# Adafruit_Circuit_Playground_Bluefruit.net
KiCad netlist of a schematic drawn in EAGLE
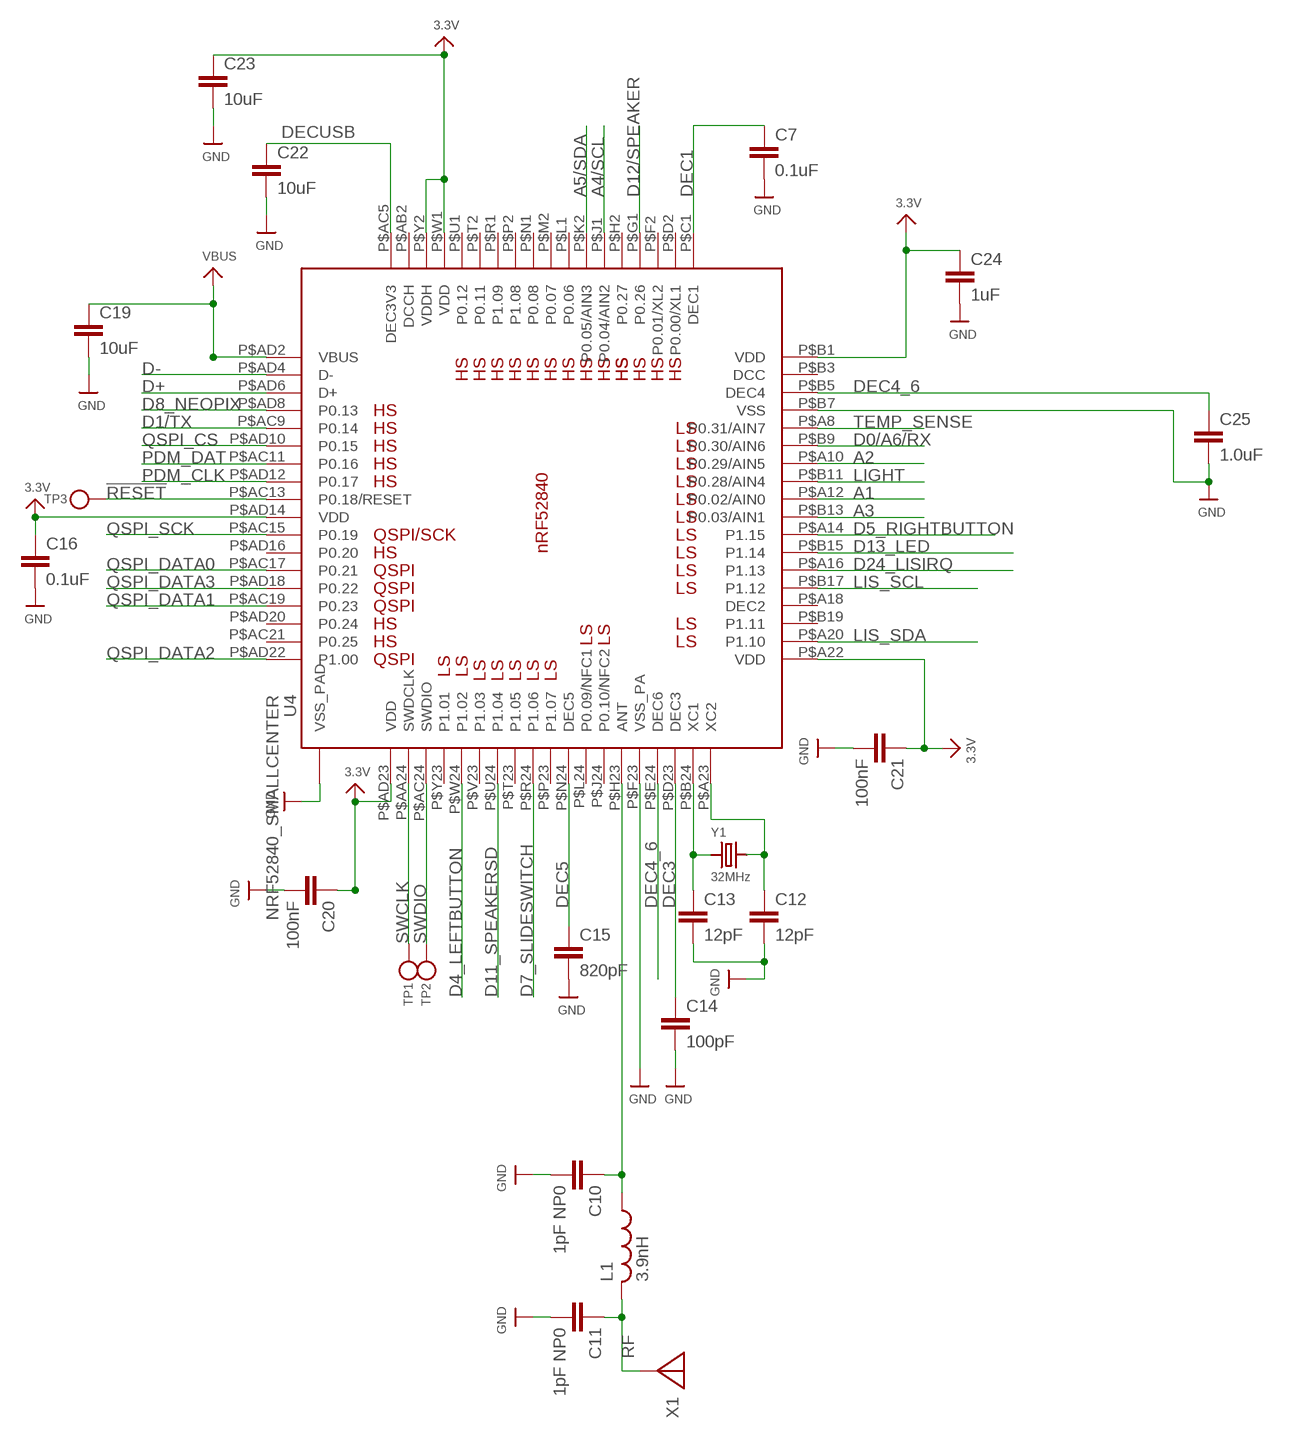
[diagram p0: schematic, sheet 1, part 1 of 2]
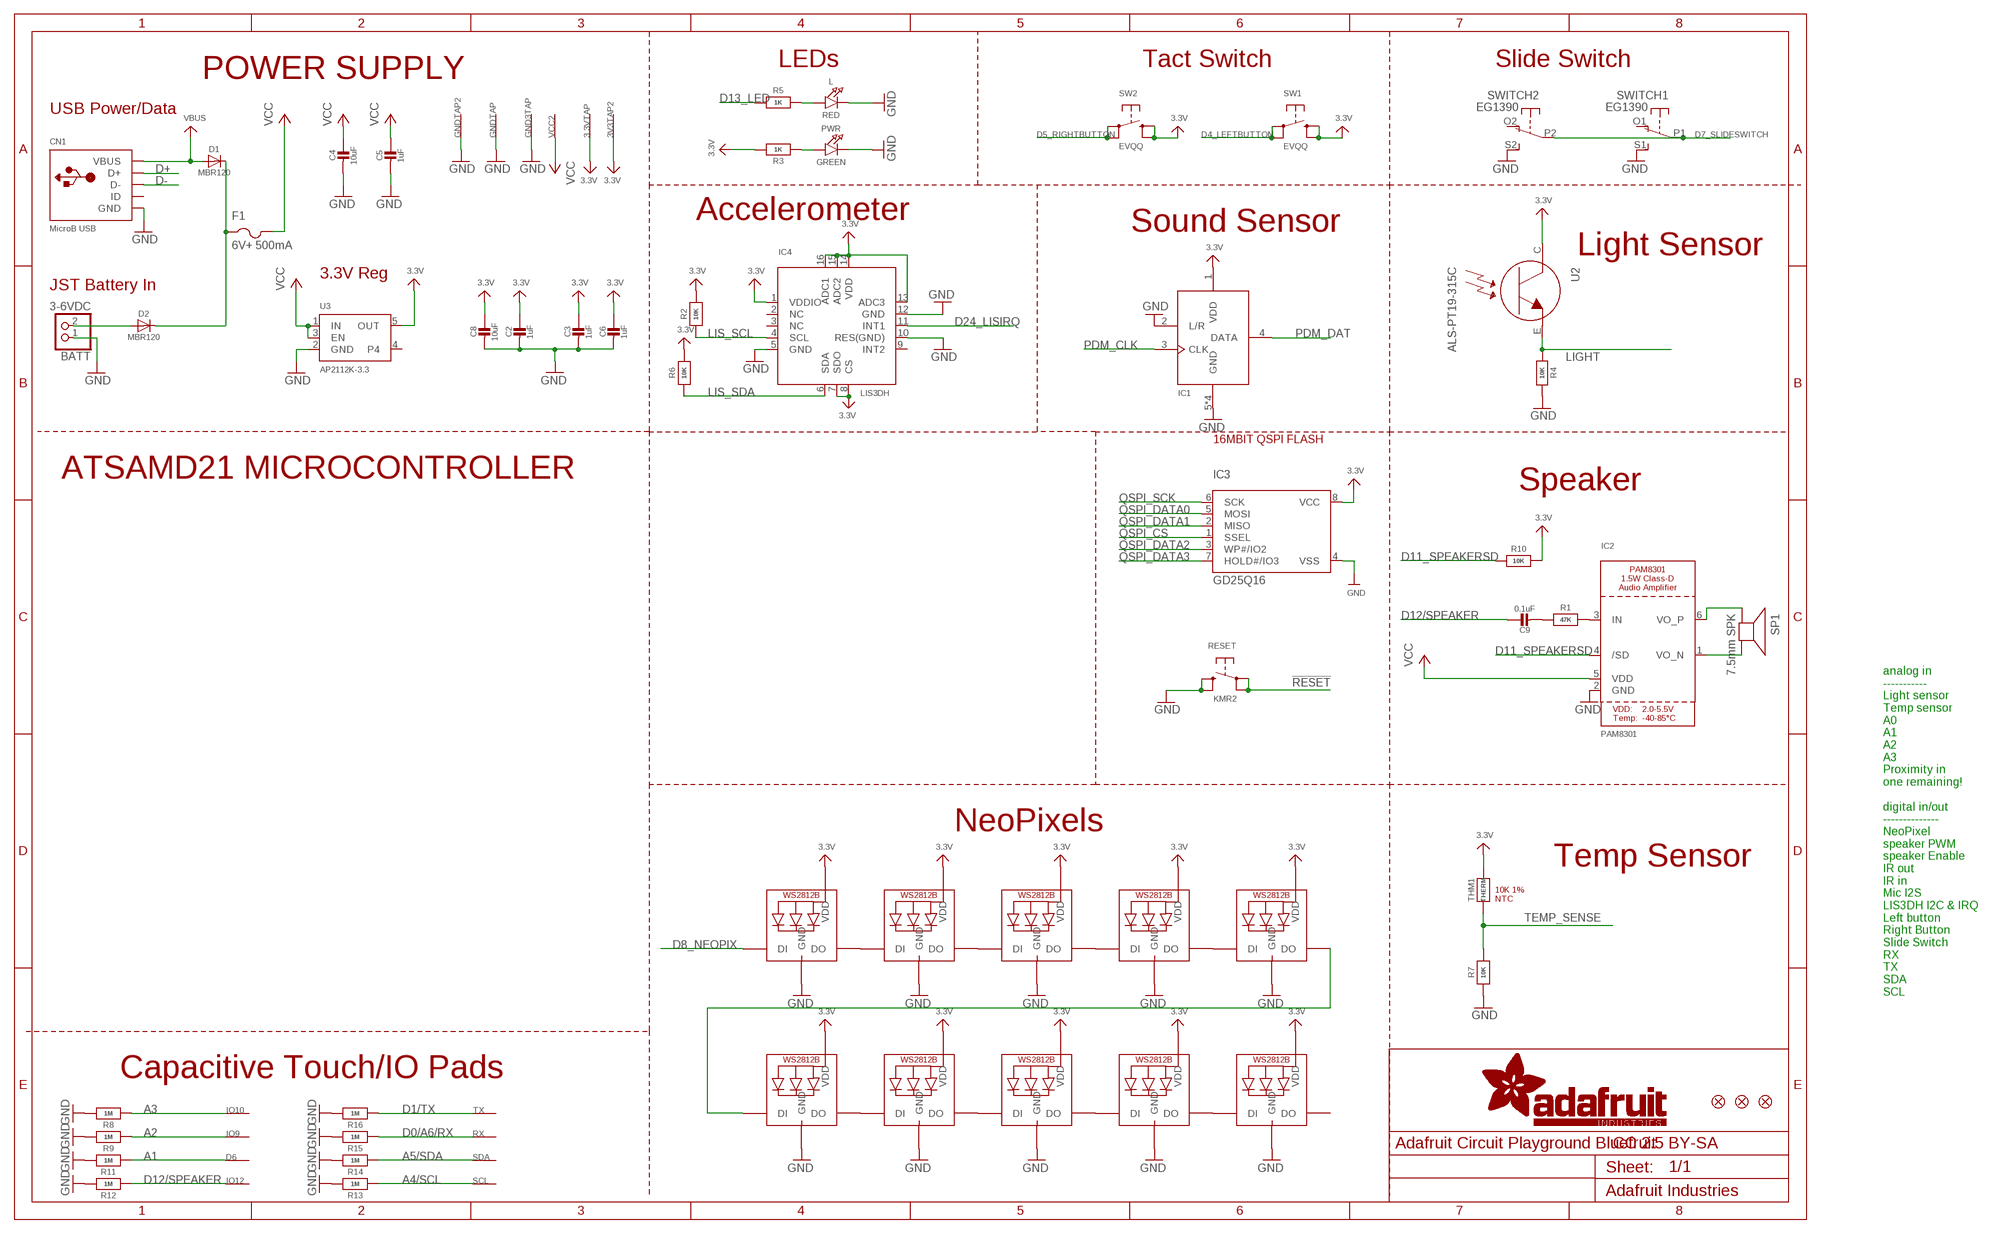
[diagram p1: schematic, sheet 1, part 2 of 2]

(export (version "E")
  (design (tool "Eeschema 10.0.6"))
  (components
    (comp (ref "3.3VTAP")
      (value "SEWTAP-ALLIGATOR")
      (footprint "eagle-import:SEWALLI")
      (libsource (lib "eagle-import") (part "SEWTAP-ALLIGATOR"))
    )
    (comp (ref "3V3TAP2")
      (value "SEWTAP-ALLIGATOR")
      (footprint "eagle-import:SEWALLI")
      (libsource (lib "eagle-import") (part "SEWTAP-ALLIGATOR"))
    )
    (comp (ref "BATT")
      (value "3-6VDC")
      (footprint "eagle-import:JSTPH2")
      (libsource (lib "eagle-import") (part "CON_JST_PH_2PIN"))
    )
    (comp (ref "C2")
      (value "1uF")
      (footprint "eagle-import:0603-NO")
      (libsource (lib "eagle-import") (part "CAP_CERAMIC0603_NO"))
    )
    (comp (ref "C3")
      (value "1uF")
      (footprint "eagle-import:0603-NO")
      (libsource (lib "eagle-import") (part "CAP_CERAMIC0603_NO"))
    )
    (comp (ref "C4")
      (value "10uF")
      (footprint "eagle-import:0805-NO")
      (libsource (lib "eagle-import") (part "CAP_CERAMIC0805-NOOUTLINE"))
    )
    (comp (ref "C5")
      (value "1uF")
      (footprint "eagle-import:0603-NO")
      (libsource (lib "eagle-import") (part "CAP_CERAMIC0603_NO"))
    )
    (comp (ref "C6")
      (value "1uF")
      (footprint "eagle-import:0603-NO")
      (libsource (lib "eagle-import") (part "CAP_CERAMIC0603_NO"))
    )
    (comp (ref "C7")
      (value "0.1uF")
      (footprint "eagle-import:RESC0603_N")
      (libsource (lib "eagle-import") (part "CAPACITOR_0603_N"))
    )
    (comp (ref "C8")
      (value "10uF")
      (footprint "eagle-import:0805-NO")
      (libsource (lib "eagle-import") (part "CAP_CERAMIC0805-NOOUTLINE"))
    )
    (comp (ref "C9")
      (value "0.1uF")
      (footprint "eagle-import:0603-NO")
      (libsource (lib "eagle-import") (part "CAP_CERAMIC0603_NO"))
    )
    (comp (ref "C10")
      (value "1pF NP0")
      (footprint "eagle-import:RESC0402_N")
      (libsource (lib "eagle-import") (part "CAPACITOR_0402_N"))
    )
    (comp (ref "C11")
      (value "1pF NP0")
      (footprint "eagle-import:RESC0402_N")
      (libsource (lib "eagle-import") (part "CAPACITOR_0402_N"))
    )
    (comp (ref "C12")
      (value "12pF")
      (footprint "eagle-import:RESC0402_N")
      (libsource (lib "eagle-import") (part "CAPACITOR_0402_N"))
    )
    (comp (ref "C13")
      (value "12pF")
      (footprint "eagle-import:RESC0402_N")
      (libsource (lib "eagle-import") (part "CAPACITOR_0402_N"))
    )
    (comp (ref "C14")
      (value "100pF")
      (footprint "eagle-import:RESC0402_N")
      (libsource (lib "eagle-import") (part "CAPACITOR_0402_N"))
    )
    (comp (ref "C15")
      (value "820pF")
      (footprint "eagle-import:RESC0402_N")
      (libsource (lib "eagle-import") (part "CAPACITOR_0402_N"))
    )
    (comp (ref "C16")
      (value "0.1uF")
      (footprint "eagle-import:RESC0402_N")
      (libsource (lib "eagle-import") (part "CAPACITOR_0402_N"))
    )
    (comp (ref "C19")
      (value "10uF")
      (footprint "eagle-import:RESC0805_N")
      (libsource (lib "eagle-import") (part "CAPACITOR_0805_N"))
    )
    (comp (ref "C20")
      (value "100nF")
      (footprint "eagle-import:RESC0402_N")
      (libsource (lib "eagle-import") (part "CAPACITOR_0402_N"))
    )
    (comp (ref "C21")
      (value "100nF")
      (footprint "eagle-import:RESC0402_N")
      (libsource (lib "eagle-import") (part "CAPACITOR_0402_N"))
    )
    (comp (ref "C22")
      (value "10uF")
      (footprint "eagle-import:RESC0805_N")
      (libsource (lib "eagle-import") (part "CAPACITOR_0805_N"))
    )
    (comp (ref "C23")
      (value "10uF")
      (footprint "eagle-import:RESC0805_N")
      (libsource (lib "eagle-import") (part "CAPACITOR_0805_N"))
    )
    (comp (ref "C24")
      (value "1uF")
      (footprint "eagle-import:RESC0603_N")
      (libsource (lib "eagle-import") (part "CAPACITOR_0603_N"))
    )
    (comp (ref "C25")
      (value "1.0uF")
      (footprint "eagle-import:RESC0603_N")
      (libsource (lib "eagle-import") (part "CAPACITOR_0603_N"))
    )
    (comp (ref "CN1")
      (value "MicroB USB")
      (footprint "eagle-import:4UCONN_20329_V2")
      (libsource (lib "eagle-import") (part "USB_MICRO_20329_V2"))
    )
    (comp (ref "D1")
      (value "MBR120")
      (footprint "eagle-import:SOD-123")
      (libsource (lib "eagle-import") (part "DIODESOD-123"))
    )
    (comp (ref "D2")
      (value "MBR120")
      (footprint "eagle-import:SOD-123")
      (libsource (lib "eagle-import") (part "DIODESOD-123"))
    )
    (comp (ref "D6")
      (value "SEWTAP-ALLIGATOR")
      (footprint "eagle-import:SEWALLI")
      (libsource (lib "eagle-import") (part "SEWTAP-ALLIGATOR"))
    )
    (comp (ref "F1")
      (value "6V+ 500mA")
      (footprint "eagle-import:R1206")
      (libsource (lib "eagle-import") (part "PTCFUSE-1206"))
    )
    (comp (ref "GND3TAP")
      (value "SEWTAP-ALLIGATOR")
      (footprint "eagle-import:SEWALLI")
      (libsource (lib "eagle-import") (part "SEWTAP-ALLIGATOR"))
    )
    (comp (ref "GNDTAP")
      (value "SEWTAP-ALLIGATOR")
      (footprint "eagle-import:SEWALLI")
      (libsource (lib "eagle-import") (part "SEWTAP-ALLIGATOR"))
    )
    (comp (ref "GNDTAP2")
      (value "SEWTAP-ALLIGATOR")
      (footprint "eagle-import:SEWALLI")
      (libsource (lib "eagle-import") (part "SEWTAP-ALLIGATOR"))
    )
    (comp (ref "IC1")
      (value "MIC_PDM")
      (footprint "eagle-import:SPK0415HM4H")
      (libsource (lib "eagle-import") (part "MIC_PDM_SPK0415"))
    )
    (comp (ref "IC2")
      (value "PAM8301")
      (footprint "eagle-import:SOT23-6")
      (libsource (lib "eagle-import") (part "PAM8301"))
    )
    (comp (ref "IC3")
      (value "GD25Q16")
      (footprint "eagle-import:USON8")
      (libsource (lib "eagle-import") (part "SPIFLASH_8PINUX"))
    )
    (comp (ref "IC4")
      (value "LIS3DH")
      (footprint "eagle-import:LGA16_3X3MM")
      (libsource (lib "eagle-import") (part "ACCEL_LIS3DHTR"))
    )
    (comp (ref "IO9")
      (value "SEWTAP-ALLIGATOR")
      (footprint "eagle-import:SEWALLI")
      (libsource (lib "eagle-import") (part "SEWTAP-ALLIGATOR"))
    )
    (comp (ref "IO10")
      (value "SEWTAP-ALLIGATOR")
      (footprint "eagle-import:SEWALLI")
      (libsource (lib "eagle-import") (part "SEWTAP-ALLIGATOR"))
    )
    (comp (ref "IO12")
      (value "SEWTAP-ALLIGATOR")
      (footprint "eagle-import:SEWALLI")
      (libsource (lib "eagle-import") (part "SEWTAP-ALLIGATOR"))
    )
    (comp (ref "L")
      (value "RED")
      (footprint "eagle-import:CHIPLED_0805_NOOUTLINE")
      (libsource (lib "eagle-import") (part "LED0805_NOOUTLINE"))
    )
    (comp (ref "L1")
      (value "3.9nH")
      (footprint "eagle-import:RESC0402_N")
      (libsource (lib "eagle-import") (part "INDUCTOR_0402_N"))
    )
    (comp (ref "LED1")
      (value "WS2812B3535")
      (footprint "eagle-import:LED3535")
      (libsource (lib "eagle-import") (part "WS2812B3535"))
    )
    (comp (ref "LED2")
      (value "WS2812B3535")
      (footprint "eagle-import:LED3535")
      (libsource (lib "eagle-import") (part "WS2812B3535"))
    )
    (comp (ref "LED3")
      (value "WS2812B3535")
      (footprint "eagle-import:LED3535")
      (libsource (lib "eagle-import") (part "WS2812B3535"))
    )
    (comp (ref "LED4")
      (value "WS2812B3535")
      (footprint "eagle-import:LED3535")
      (libsource (lib "eagle-import") (part "WS2812B3535"))
    )
    (comp (ref "LED5")
      (value "WS2812B3535")
      (footprint "eagle-import:LED3535")
      (libsource (lib "eagle-import") (part "WS2812B3535"))
    )
    (comp (ref "LED6")
      (value "WS2812B3535")
      (footprint "eagle-import:LED3535")
      (libsource (lib "eagle-import") (part "WS2812B3535"))
    )
    (comp (ref "LED7")
      (value "WS2812B3535")
      (footprint "eagle-import:LED3535")
      (libsource (lib "eagle-import") (part "WS2812B3535"))
    )
    (comp (ref "LED8")
      (value "WS2812B3535")
      (footprint "eagle-import:LED3535")
      (libsource (lib "eagle-import") (part "WS2812B3535"))
    )
    (comp (ref "LED9")
      (value "WS2812B3535")
      (footprint "eagle-import:LED3535")
      (libsource (lib "eagle-import") (part "WS2812B3535"))
    )
    (comp (ref "LED10")
      (value "WS2812B3535")
      (footprint "eagle-import:LED3535")
      (libsource (lib "eagle-import") (part "WS2812B3535"))
    )
    (comp (ref "PWR")
      (value "GREEN")
      (footprint "eagle-import:CHIPLED_0805_NOOUTLINE")
      (libsource (lib "eagle-import") (part "LED0805_NOOUTLINE"))
    )
    (comp (ref "R1")
      (value "47K")
      (footprint "eagle-import:0603-NO")
      (libsource (lib "eagle-import") (part "RESISTOR_0603_NOOUT"))
    )
    (comp (ref "R2")
      (value "10K")
      (footprint "eagle-import:0603-NO")
      (libsource (lib "eagle-import") (part "RESISTOR_0603_NOOUT"))
    )
    (comp (ref "R3")
      (value "1K")
      (footprint "eagle-import:0603-NO")
      (libsource (lib "eagle-import") (part "RESISTOR_0603_NOOUT"))
    )
    (comp (ref "R4")
      (value "10K")
      (footprint "eagle-import:0603-NO")
      (libsource (lib "eagle-import") (part "RESISTOR_0603_NOOUT"))
    )
    (comp (ref "R5")
      (value "1K")
      (footprint "eagle-import:0603-NO")
      (libsource (lib "eagle-import") (part "RESISTOR_0603_NOOUT"))
    )
    (comp (ref "R6")
      (value "10K")
      (footprint "eagle-import:0603-NO")
      (libsource (lib "eagle-import") (part "RESISTOR_0603_NOOUT"))
    )
    (comp (ref "R7")
      (value "10K")
      (footprint "eagle-import:0603-NO")
      (libsource (lib "eagle-import") (part "RESISTOR_0603_NOOUT"))
    )
    (comp (ref "R8")
      (value "1M")
      (footprint "eagle-import:0603-NO")
      (libsource (lib "eagle-import") (part "RESISTOR_0603_NOOUT"))
    )
    (comp (ref "R9")
      (value "1M")
      (footprint "eagle-import:0603-NO")
      (libsource (lib "eagle-import") (part "RESISTOR_0603_NOOUT"))
    )
    (comp (ref "R10")
      (value "10K")
      (footprint "eagle-import:0603-NO")
      (libsource (lib "eagle-import") (part "RESISTOR_0603_NOOUT"))
    )
    (comp (ref "R11")
      (value "1M")
      (footprint "eagle-import:0603-NO")
      (libsource (lib "eagle-import") (part "RESISTOR_0603_NOOUT"))
    )
    (comp (ref "R12")
      (value "1M")
      (footprint "eagle-import:0603-NO")
      (libsource (lib "eagle-import") (part "RESISTOR_0603_NOOUT"))
    )
    (comp (ref "R13")
      (value "1M")
      (footprint "eagle-import:0603-NO")
      (libsource (lib "eagle-import") (part "RESISTOR_0603_NOOUT"))
    )
    (comp (ref "R14")
      (value "1M")
      (footprint "eagle-import:0603-NO")
      (libsource (lib "eagle-import") (part "RESISTOR_0603_NOOUT"))
    )
    (comp (ref "R15")
      (value "1M")
      (footprint "eagle-import:0603-NO")
      (libsource (lib "eagle-import") (part "RESISTOR_0603_NOOUT"))
    )
    (comp (ref "R16")
      (value "1M")
      (footprint "eagle-import:0603-NO")
      (libsource (lib "eagle-import") (part "RESISTOR_0603_NOOUT"))
    )
    (comp (ref "RESET")
      (value "KMR2")
      (footprint "eagle-import:BTN_KMR2_4.6X2.8")
      (libsource (lib "eagle-import") (part "SWITCH_TACT_SMT4.6X2.8"))
    )
    (comp (ref "RX")
      (value "SEWTAP-ALLIGATOR")
      (footprint "eagle-import:SEWALLI")
      (libsource (lib "eagle-import") (part "SEWTAP-ALLIGATOR"))
    )
    (comp (ref "SCL")
      (value "SEWTAP-ALLIGATOR")
      (footprint "eagle-import:SEWALLI")
      (libsource (lib "eagle-import") (part "SEWTAP-ALLIGATOR"))
    )
    (comp (ref "SDA")
      (value "SEWTAP-ALLIGATOR")
      (footprint "eagle-import:SEWALLI")
      (libsource (lib "eagle-import") (part "SEWTAP-ALLIGATOR"))
    )
    (comp (ref "SP1")
      (value "7.5mm SPK")
      (footprint "eagle-import:BUZZER_SMT_7.5MM")
      (libsource (lib "eagle-import") (part "SPEAKER_7.5MM"))
    )
    (comp (ref "SW1")
      (value "EVQQ")
      (footprint "eagle-import:EVQ-Q2_SMALLER")
      (libsource (lib "eagle-import") (part "SWITCH_TACT_SMT_EVQQ2_SMALL"))
    )
    (comp (ref "SW2")
      (value "EVQQ")
      (footprint "eagle-import:EVQ-Q2_SMALLER")
      (libsource (lib "eagle-import") (part "SWITCH_TACT_SMT_EVQQ2_SMALL"))
    )
    (comp (ref "SWITCH")
      (value "EG1390")
      (footprint "eagle-import:EG1390")
      (libsource (lib "eagle-import") (part "DPDT-EG1390"))
    )
    (comp (ref "THM1")
      (value "THERM")
      (footprint "eagle-import:_0402")
      (libsource (lib "eagle-import") (part "RESISTOR_0402"))
    )
    (comp (ref "TP1")
      (value "TESTPOINTROUND1.5MMNO")
      (footprint "eagle-import:TESTPOINT_ROUND_1.5MM_NO")
      (libsource (lib "eagle-import") (part "TESTPOINTROUND1.5MMNO"))
    )
    (comp (ref "TP2")
      (value "TESTPOINTROUND1.5MMNO")
      (footprint "eagle-import:TESTPOINT_ROUND_1.5MM_NO")
      (libsource (lib "eagle-import") (part "TESTPOINTROUND1.5MMNO"))
    )
    (comp (ref "TP3")
      (value "TESTPOINTROUND1.5MMNO")
      (footprint "eagle-import:TESTPOINT_ROUND_1.5MM_NO")
      (libsource (lib "eagle-import") (part "TESTPOINTROUND1.5MMNO"))
    )
    (comp (ref "TX")
      (value "SEWTAP-ALLIGATOR")
      (footprint "eagle-import:SEWALLI")
      (libsource (lib "eagle-import") (part "SEWTAP-ALLIGATOR"))
    )
    (comp (ref "U$2")
      (value "FIDUCIAL_1MM")
      (footprint "eagle-import:FIDUCIAL_1MM")
      (libsource (lib "eagle-import") (part "FIDUCIAL_1MM"))
    )
    (comp (ref "U$3")
      (value "FIDUCIAL_1MM")
      (footprint "eagle-import:FIDUCIAL_1MM")
      (fields (field (name "BOM") "EXCLUDE"))
      (libsource (lib "eagle-import") (part "FIDUCIAL_1MM"))
    )
    (comp (ref "U$6")
      (value "FIDUCIAL_1MM")
      (footprint "eagle-import:FIDUCIAL_1MM")
      (libsource (lib "eagle-import") (part "FIDUCIAL_1MM"))
    )
    (comp (ref "U2")
      (value "ALS-PT19-315C")
      (footprint "eagle-import:ALS-PT19-315C")
      (libsource (lib "eagle-import") (part "PHOTOTRANSISTOR_PT19-315C"))
    )
    (comp (ref "U3")
      (value "AP2112K-3.3")
      (footprint "eagle-import:SOT23-5")
      (libsource (lib "eagle-import") (part "VREG_SOT23-5"))
    )
    (comp (ref "U4")
      (value "NRF52840_SMALLCENTER")
      (footprint "eagle-import:AQFN50P700X800X85_HS-74N_SMALLCENTER")
      (libsource (lib "eagle-import") (part "NRF52840_SMALLCENTER"))
    )
    (comp (ref "VCC2")
      (value "SEWTAP-ALLIGATOR")
      (footprint "eagle-import:SEWALLI")
      (libsource (lib "eagle-import") (part "SEWTAP-ALLIGATOR"))
    )
    (comp (ref "X1")
      (value "ANTENNA_JOHANSON_2450AT18B100")
      (footprint "eagle-import:ANT_2450AT18B100")
      (libsource (lib "eagle-import") (part "ANTENNA_JOHANSON_2450AT18B100"))
    )
    (comp (ref "Y1")
      (value "32MHz")
      (footprint "eagle-import:CRYSTAL_2.5X2")
      (libsource (lib "eagle-import") (part "CRYSTAL2.5X2.0"))
    )
  )
  (nets
    (net (code "1") (name "/A1") (class "Default")
      (node (ref "D6") (pin "P$1") (pinfunction "SEW_P$1") (pintype "bidirectional"))
      (node (ref "R11") (pin "1") (pinfunction "1_1") (pintype "passive"))
      (node (ref "U4") (pin "P$A12") (pinfunction "P0.02/AIN0_P$A12") (pintype "bidirectional"))
    )
    (net (code "2") (name "/A2") (class "Default")
      (node (ref "IO9") (pin "P$1") (pinfunction "SEW_P$1") (pintype "bidirectional"))
      (node (ref "R9") (pin "1") (pinfunction "1_1") (pintype "passive"))
      (node (ref "U4") (pin "P$A10") (pinfunction "P0.29/AIN5_P$A10") (pintype "bidirectional"))
    )
    (net (code "3") (name "/A3") (class "Default")
      (node (ref "IO10") (pin "P$1") (pinfunction "SEW_P$1") (pintype "bidirectional"))
      (node (ref "R8") (pin "1") (pinfunction "1_1") (pintype "passive"))
      (node (ref "U4") (pin "P$B13") (pinfunction "P0.03/AIN1_P$B13") (pintype "bidirectional"))
    )
    (net (code "4") (name "/A4{slash}SCL") (class "Default")
      (node (ref "R13") (pin "1") (pinfunction "1_1") (pintype "passive"))
      (node (ref "SCL") (pin "P$1") (pinfunction "SEW_P$1") (pintype "bidirectional"))
      (node (ref "U4") (pin "P$J1") (pinfunction "P0.04/AIN2_P$J1") (pintype "bidirectional"))
    )
    (net (code "5") (name "/A5{slash}SDA") (class "Default")
      (node (ref "R14") (pin "1") (pinfunction "1_1") (pintype "passive"))
      (node (ref "SDA") (pin "P$1") (pinfunction "SEW_P$1") (pintype "bidirectional"))
      (node (ref "U4") (pin "P$K2") (pinfunction "P0.05/AIN3_P$K2") (pintype "bidirectional"))
    )
    (net (code "6") (name "/D+") (class "Default")
      (node (ref "CN1") (pin "D+") (pinfunction "D+_D+") (pintype "bidirectional"))
      (node (ref "U4") (pin "P$AD6") (pinfunction "D+_P$AD6") (pintype "bidirectional"))
    )
    (net (code "7") (name "/D-") (class "Default")
      (node (ref "CN1") (pin "D-") (pinfunction "D-_D-") (pintype "bidirectional"))
      (node (ref "U4") (pin "P$AD4") (pinfunction "D-_P$AD4") (pintype "bidirectional"))
    )
    (net (code "8") (name "/D0{slash}A6{slash}RX") (class "Default")
      (node (ref "R15") (pin "1") (pinfunction "1_1") (pintype "passive"))
      (node (ref "RX") (pin "P$1") (pinfunction "SEW_P$1") (pintype "bidirectional"))
      (node (ref "U4") (pin "P$B9") (pinfunction "P0.30/AIN6_P$B9") (pintype "bidirectional"))
    )
    (net (code "9") (name "/D1{slash}TX") (class "Default")
      (node (ref "R16") (pin "1") (pinfunction "1_1") (pintype "passive"))
      (node (ref "TX") (pin "P$1") (pinfunction "SEW_P$1") (pintype "bidirectional"))
      (node (ref "U4") (pin "P$AC9") (pinfunction "P0.14_P$AC9") (pintype "bidirectional"))
    )
    (net (code "10") (name "/D4_LEFTBUTTON") (class "Default")
      (node (ref "SW1") (pin "A") (pinfunction "P_A") (pintype "passive"))
      (node (ref "SW1") (pin "A'") (pinfunction "P1_A'") (pintype "passive"))
      (node (ref "U4") (pin "P$W24") (pinfunction "P1.02_P$W24") (pintype "bidirectional"))
    )
    (net (code "11") (name "/D5_RIGHTBUTTON") (class "Default")
      (node (ref "SW2") (pin "A") (pinfunction "P_A") (pintype "passive"))
      (node (ref "SW2") (pin "A'") (pinfunction "P1_A'") (pintype "passive"))
      (node (ref "U4") (pin "P$A14") (pinfunction "P1.15_P$A14") (pintype "bidirectional"))
    )
    (net (code "12") (name "/D7_SLIDESWITCH") (class "Default")
      (node (ref "SWITCH") (pin "P1") (pinfunction "P_P1") (pintype "passive"))
      (node (ref "SWITCH") (pin "P2") (pinfunction "P_P2") (pintype "passive"))
      (node (ref "U4") (pin "P$R24") (pinfunction "P1.06_P$R24") (pintype "bidirectional"))
    )
    (net (code "13") (name "/D8_NEOPIX") (class "Default")
      (node (ref "LED6") (pin "1") (pinfunction "DI_1") (pintype "input"))
      (node (ref "U4") (pin "P$AD8") (pinfunction "P0.13_P$AD8") (pintype "bidirectional"))
    )
    (net (code "14") (name "/D11_SPEAKERSD") (class "Default")
      (node (ref "IC2") (pin "4") (pinfunction "/SD_4") (pintype "input"))
      (node (ref "R10") (pin "1") (pinfunction "1_1") (pintype "passive"))
      (node (ref "U4") (pin "P$U24") (pinfunction "P1.04_P$U24") (pintype "bidirectional"))
    )
    (net (code "15") (name "/D12{slash}SPEAKER") (class "Default")
      (node (ref "C9") (pin "1") (pinfunction "1_1") (pintype "passive"))
      (node (ref "IO12") (pin "P$1") (pinfunction "SEW_P$1") (pintype "bidirectional"))
      (node (ref "R12") (pin "1") (pinfunction "1_1") (pintype "passive"))
      (node (ref "U4") (pin "P$G1") (pinfunction "P0.26_P$G1") (pintype "bidirectional"))
    )
    (net (code "16") (name "/D13_LED") (class "Default")
      (node (ref "R5") (pin "1") (pinfunction "1_1") (pintype "passive"))
      (node (ref "U4") (pin "P$B15") (pinfunction "P1.14_P$B15") (pintype "bidirectional"))
    )
    (net (code "17") (name "/D24_LISIRQ") (class "Default")
      (node (ref "IC4") (pin "11") (pinfunction "INT1_11") (pintype "output"))
      (node (ref "U4") (pin "P$A16") (pinfunction "P1.13_P$A16") (pintype "bidirectional"))
    )
    (net (code "18") (name "/DEC1") (class "Default")
      (node (ref "C7") (pin "1") (pinfunction "1_1") (pintype "passive"))
      (node (ref "U4") (pin "P$C1") (pinfunction "DEC1_P$C1") (pintype "power_in"))
    )
    (net (code "19") (name "/DEC3") (class "Default")
      (node (ref "C14") (pin "1") (pinfunction "1_1") (pintype "passive"))
      (node (ref "U4") (pin "P$D23") (pinfunction "DEC3_P$D23") (pintype "bidirectional"))
    )
    (net (code "20") (name "/DEC4_6") (class "Default")
      (node (ref "C25") (pin "1") (pinfunction "1_1") (pintype "passive"))
      (node (ref "U4") (pin "P$B5") (pinfunction "DEC4_P$B5") (pintype "power_in"))
      (node (ref "U4") (pin "P$E24") (pinfunction "DEC6_P$E24") (pintype "bidirectional"))
    )
    (net (code "21") (name "/DEC5") (class "Default")
      (node (ref "C15") (pin "1") (pinfunction "1_1") (pintype "passive"))
      (node (ref "U4") (pin "P$N24") (pinfunction "DEC5_P$N24") (pintype "bidirectional"))
    )
    (net (code "22") (name "/DECUSB") (class "Default")
      (node (ref "C22") (pin "1") (pinfunction "1_1") (pintype "passive"))
      (node (ref "U4") (pin "P$AC5") (pinfunction "DEC3V3_P$AC5") (pintype "bidirectional"))
    )
    (net (code "23") (name "/LIGHT") (class "Default")
      (node (ref "R4") (pin "2") (pinfunction "2_2") (pintype "passive"))
      (node (ref "U2") (pin "E") (pinfunction "E_E") (pintype "bidirectional"))
      (node (ref "U4") (pin "P$B11") (pinfunction "P0.28/AIN4_P$B11") (pintype "bidirectional"))
    )
    (net (code "24") (name "/LIS_SCL") (class "Default")
      (node (ref "IC4") (pin "4") (pinfunction "SCL_4") (pintype "bidirectional"))
      (node (ref "R2") (pin "1") (pinfunction "1_1") (pintype "passive"))
      (node (ref "U4") (pin "P$B17") (pinfunction "P1.12_P$B17") (pintype "bidirectional"))
    )
    (net (code "25") (name "/LIS_SDA") (class "Default")
      (node (ref "IC4") (pin "6") (pinfunction "SDA_6") (pintype "bidirectional"))
      (node (ref "R6") (pin "1") (pinfunction "1_1") (pintype "passive"))
      (node (ref "U4") (pin "P$A20") (pinfunction "P1.10_P$A20") (pintype "bidirectional"))
    )
    (net (code "26") (name "/PDM_CLK") (class "Default")
      (node (ref "IC1") (pin "3") (pinfunction "CLK_3") (pintype "input"))
      (node (ref "U4") (pin "P$AD12") (pinfunction "P0.17_P$AD12") (pintype "bidirectional"))
    )
    (net (code "27") (name "/PDM_DAT") (class "Default")
      (node (ref "IC1") (pin "4") (pinfunction "DATA_4") (pintype "bidirectional"))
      (node (ref "U4") (pin "P$AC11") (pinfunction "P0.16_P$AC11") (pintype "bidirectional"))
    )
    (net (code "28") (name "/QSPI_CS") (class "Default")
      (node (ref "IC3") (pin "1") (pinfunction "SSEL_1") (pintype "bidirectional"))
      (node (ref "U4") (pin "P$AD10") (pinfunction "P0.15_P$AD10") (pintype "bidirectional"))
    )
    (net (code "29") (name "/QSPI_DATA0") (class "Default")
      (node (ref "IC3") (pin "5") (pinfunction "MOSI_5") (pintype "bidirectional"))
      (node (ref "U4") (pin "P$AC17") (pinfunction "P0.21_P$AC17") (pintype "bidirectional"))
    )
    (net (code "30") (name "/QSPI_DATA1") (class "Default")
      (node (ref "IC3") (pin "2") (pinfunction "MISO_2") (pintype "bidirectional"))
      (node (ref "U4") (pin "P$AC19") (pinfunction "P0.23_P$AC19") (pintype "bidirectional"))
    )
    (net (code "31") (name "/QSPI_DATA2") (class "Default")
      (node (ref "IC3") (pin "3") (pinfunction "WP#/IO2_3") (pintype "bidirectional"))
      (node (ref "U4") (pin "P$AD22") (pinfunction "P1.00_P$AD22") (pintype "bidirectional"))
    )
    (net (code "32") (name "/QSPI_DATA3") (class "Default")
      (node (ref "IC3") (pin "7") (pinfunction "HOLD#/IO3_7") (pintype "bidirectional"))
      (node (ref "U4") (pin "P$AD18") (pinfunction "P0.22_P$AD18") (pintype "bidirectional"))
    )
    (net (code "33") (name "/QSPI_SCK") (class "Default")
      (node (ref "IC3") (pin "6") (pinfunction "SCK_6") (pintype "bidirectional"))
      (node (ref "U4") (pin "P$AC15") (pinfunction "P0.19_P$AC15") (pintype "bidirectional"))
    )
    (net (code "34") (name "/RF") (class "Default")
      (node (ref "C11") (pin "1") (pinfunction "1_1") (pintype "passive"))
      (node (ref "L1") (pin "2") (pinfunction "2_2") (pintype "passive"))
      (node (ref "X1") (pin "FP") (pinfunction "P$1_FP") (pintype "passive"))
    )
    (net (code "35") (name "/SWCLK") (class "Default")
      (node (ref "TP1") (pin "P$1") (pinfunction "P$1_P$1") (pintype "bidirectional"))
      (node (ref "U4") (pin "P$AA24") (pinfunction "SWDCLK_P$AA24") (pintype "input"))
    )
    (net (code "36") (name "/SWDIO") (class "Default")
      (node (ref "TP2") (pin "P$1") (pinfunction "P$1_P$1") (pintype "bidirectional"))
      (node (ref "U4") (pin "P$AC24") (pinfunction "SWDIO_P$AC24") (pintype "bidirectional"))
    )
    (net (code "37") (name "/TEMP_SENSE") (class "Default")
      (node (ref "R7") (pin "2") (pinfunction "2_2") (pintype "passive"))
      (node (ref "THM1") (pin "1") (pinfunction "1_1") (pintype "passive"))
      (node (ref "U4") (pin "P$A8") (pinfunction "P0.31/AIN7_P$A8") (pintype "bidirectional"))
    )
    (net (code "38") (name "/~{RESET}") (class "Default")
      (node (ref "RESET") (pin "A") (pinfunction "P_A") (pintype "passive"))
      (node (ref "RESET") (pin "A'") (pinfunction "P1_A'") (pintype "passive"))
      (node (ref "TP3") (pin "P$1") (pinfunction "P$1_P$1") (pintype "bidirectional"))
      (node (ref "U4") (pin "P$AC13") (pinfunction "P0.18/RESET_P$AC13") (pintype "bidirectional"))
    )
    (net (code "39") (name "3.3V") (class "Default")
      (node (ref "3.3VTAP") (pin "P$1") (pinfunction "SEW_P$1") (pintype "bidirectional"))
      (node (ref "3V3TAP2") (pin "P$1") (pinfunction "SEW_P$1") (pintype "bidirectional"))
      (node (ref "C16") (pin "1") (pinfunction "1_1") (pintype "passive"))
      (node (ref "C2") (pin "1") (pinfunction "1_1") (pintype "passive"))
      (node (ref "C20") (pin "1") (pinfunction "1_1") (pintype "passive"))
      (node (ref "C21") (pin "1") (pinfunction "1_1") (pintype "passive"))
      (node (ref "C23") (pin "1") (pinfunction "1_1") (pintype "passive"))
      (node (ref "C24") (pin "1") (pinfunction "1_1") (pintype "passive"))
      (node (ref "C3") (pin "1") (pinfunction "1_1") (pintype "passive"))
      (node (ref "C6") (pin "1") (pinfunction "1_1") (pintype "passive"))
      (node (ref "C8") (pin "1") (pinfunction "1_1") (pintype "passive"))
      (node (ref "IC1") (pin "1") (pinfunction "VDD_1") (pintype "power_in"))
      (node (ref "IC3") (pin "8") (pinfunction "VCC_8") (pintype "bidirectional"))
      (node (ref "IC4") (pin "1") (pinfunction "VDDIO_1") (pintype "power_in"))
      (node (ref "IC4") (pin "13") (pinfunction "ADC3_13") (pintype "input"))
      (node (ref "IC4") (pin "14") (pinfunction "VDD_14") (pintype "power_in"))
      (node (ref "IC4") (pin "15") (pinfunction "ADC2_15") (pintype "input"))
      (node (ref "IC4") (pin "16") (pinfunction "ADC1_16") (pintype "input"))
      (node (ref "IC4") (pin "7") (pinfunction "SDO_7") (pintype "bidirectional"))
      (node (ref "IC4") (pin "8") (pinfunction "CS_8") (pintype "input"))
      (node (ref "LED1") (pin "2") (pinfunction "VDD_2") (pintype "power_in"))
      (node (ref "LED10") (pin "2") (pinfunction "VDD_2") (pintype "power_in"))
      (node (ref "LED2") (pin "2") (pinfunction "VDD_2") (pintype "power_in"))
      (node (ref "LED3") (pin "2") (pinfunction "VDD_2") (pintype "power_in"))
      (node (ref "LED4") (pin "2") (pinfunction "VDD_2") (pintype "power_in"))
      (node (ref "LED5") (pin "2") (pinfunction "VDD_2") (pintype "power_in"))
      (node (ref "LED6") (pin "2") (pinfunction "VDD_2") (pintype "power_in"))
      (node (ref "LED7") (pin "2") (pinfunction "VDD_2") (pintype "power_in"))
      (node (ref "LED8") (pin "2") (pinfunction "VDD_2") (pintype "power_in"))
      (node (ref "LED9") (pin "2") (pinfunction "VDD_2") (pintype "power_in"))
      (node (ref "R10") (pin "2") (pinfunction "2_2") (pintype "passive"))
      (node (ref "R2") (pin "2") (pinfunction "2_2") (pintype "passive"))
      (node (ref "R3") (pin "2") (pinfunction "2_2") (pintype "passive"))
      (node (ref "R6") (pin "2") (pinfunction "2_2") (pintype "passive"))
      (node (ref "SW1") (pin "B") (pinfunction "S_B") (pintype "passive"))
      (node (ref "SW1") (pin "B'") (pinfunction "S1_B'") (pintype "passive"))
      (node (ref "SW2") (pin "B") (pinfunction "S_B") (pintype "passive"))
      (node (ref "SW2") (pin "B'") (pinfunction "S1_B'") (pintype "passive"))
      (node (ref "THM1") (pin "2") (pinfunction "2_2") (pintype "passive"))
      (node (ref "U2") (pin "C") (pinfunction "C_C") (pintype "bidirectional"))
      (node (ref "U3") (pin "5") (pinfunction "OUT_5") (pintype "power_in"))
      (node (ref "U4") (pin "P$A22") (pinfunction "VDD_P$A22") (pintype "power_in"))
      (node (ref "U4") (pin "P$AD14") (pinfunction "VDD_P$AD14") (pintype "power_in"))
      (node (ref "U4") (pin "P$AD23") (pinfunction "VDD_P$AD23") (pintype "power_in"))
      (node (ref "U4") (pin "P$B1") (pinfunction "VDD_P$B1") (pintype "power_in"))
      (node (ref "U4") (pin "P$W1") (pinfunction "VDD_P$W1") (pintype "power_in"))
      (node (ref "U4") (pin "P$Y2") (pinfunction "VDDH_P$Y2") (pintype "power_in"))
    )
    (net (code "40") (name "GND") (class "Default")
      (node (ref "BATT") (pin "1") (pinfunction "1_1") (pintype "passive"))
      (node (ref "C10") (pin "2") (pinfunction "2_2") (pintype "passive"))
      (node (ref "C11") (pin "2") (pinfunction "2_2") (pintype "passive"))
      (node (ref "C12") (pin "2") (pinfunction "2_2") (pintype "passive"))
      (node (ref "C13") (pin "2") (pinfunction "2_2") (pintype "passive"))
      (node (ref "C14") (pin "2") (pinfunction "2_2") (pintype "passive"))
      (node (ref "C15") (pin "2") (pinfunction "2_2") (pintype "passive"))
      (node (ref "C16") (pin "2") (pinfunction "2_2") (pintype "passive"))
      (node (ref "C19") (pin "2") (pinfunction "2_2") (pintype "passive"))
      (node (ref "C2") (pin "2") (pinfunction "2_2") (pintype "passive"))
      (node (ref "C20") (pin "2") (pinfunction "2_2") (pintype "passive"))
      (node (ref "C21") (pin "2") (pinfunction "2_2") (pintype "passive"))
      (node (ref "C22") (pin "2") (pinfunction "2_2") (pintype "passive"))
      (node (ref "C23") (pin "2") (pinfunction "2_2") (pintype "passive"))
      (node (ref "C24") (pin "2") (pinfunction "2_2") (pintype "passive"))
      (node (ref "C25") (pin "2") (pinfunction "2_2") (pintype "passive"))
      (node (ref "C3") (pin "2") (pinfunction "2_2") (pintype "passive"))
      (node (ref "C4") (pin "2") (pinfunction "2_2") (pintype "passive"))
      (node (ref "C5") (pin "2") (pinfunction "2_2") (pintype "passive"))
      (node (ref "C6") (pin "2") (pinfunction "2_2") (pintype "passive"))
      (node (ref "C7") (pin "2") (pinfunction "2_2") (pintype "passive"))
      (node (ref "C8") (pin "2") (pinfunction "2_2") (pintype "passive"))
      (node (ref "CN1") (pin "BASE@1") (pinfunction "GND_BASE@1") (pintype "power_in"))
      (node (ref "CN1") (pin "BASE@2") (pinfunction "GND_BASE@2") (pintype "power_in"))
      (node (ref "CN1") (pin "GND") (pinfunction "GND_GND") (pintype "power_in"))
      (node (ref "CN1") (pin "SPRT@1") (pinfunction "GND_SPRT@1") (pintype "power_in"))
      (node (ref "CN1") (pin "SPRT@2") (pinfunction "GND_SPRT@2") (pintype "power_in"))
      (node (ref "CN1") (pin "SPRT@3") (pinfunction "GND_SPRT@3") (pintype "power_in"))
      (node (ref "CN1") (pin "SPRT@4") (pinfunction "GND_SPRT@4") (pintype "power_in"))
      (node (ref "GND3TAP") (pin "P$1") (pinfunction "SEW_P$1") (pintype "bidirectional"))
      (node (ref "GNDTAP") (pin "P$1") (pinfunction "SEW_P$1") (pintype "bidirectional"))
      (node (ref "GNDTAP2") (pin "P$1") (pinfunction "SEW_P$1") (pintype "bidirectional"))
      (node (ref "IC1") (pin "2") (pinfunction "L/R_2") (pintype "input"))
      (node (ref "IC1") (pin "5") (pinfunction "GND_5") (pintype "power_in"))
      (node (ref "IC1") (pin "6") (pinfunction "GND_6") (pintype "power_in"))
      (node (ref "IC1") (pin "7") (pinfunction "GND_7") (pintype "power_in"))
      (node (ref "IC1") (pin "8") (pinfunction "GND_8") (pintype "power_in"))
      (node (ref "IC2") (pin "2") (pinfunction "GND_2") (pintype "power_in"))
      (node (ref "IC3") (pin "4") (pinfunction "VSS_4") (pintype "bidirectional"))
      (node (ref "IC4") (pin "10") (pinfunction "RES(GND)_10") (pintype "bidirectional"))
      (node (ref "IC4") (pin "12") (pinfunction "GND_12") (pintype "power_in"))
      (node (ref "IC4") (pin "5") (pinfunction "GND_5") (pintype "power_in"))
      (node (ref "L") (pin "C") (pinfunction "C_C") (pintype "passive"))
      (node (ref "LED1") (pin "4") (pinfunction "GND_4") (pintype "power_in"))
      (node (ref "LED10") (pin "4") (pinfunction "GND_4") (pintype "power_in"))
      (node (ref "LED2") (pin "4") (pinfunction "GND_4") (pintype "power_in"))
      (node (ref "LED3") (pin "4") (pinfunction "GND_4") (pintype "power_in"))
      (node (ref "LED4") (pin "4") (pinfunction "GND_4") (pintype "power_in"))
      (node (ref "LED5") (pin "4") (pinfunction "GND_4") (pintype "power_in"))
      (node (ref "LED6") (pin "4") (pinfunction "GND_4") (pintype "power_in"))
      (node (ref "LED7") (pin "4") (pinfunction "GND_4") (pintype "power_in"))
      (node (ref "LED8") (pin "4") (pinfunction "GND_4") (pintype "power_in"))
      (node (ref "LED9") (pin "4") (pinfunction "GND_4") (pintype "power_in"))
      (node (ref "PWR") (pin "C") (pinfunction "C_C") (pintype "passive"))
      (node (ref "R11") (pin "2") (pinfunction "2_2") (pintype "passive"))
      (node (ref "R12") (pin "2") (pinfunction "2_2") (pintype "passive"))
      (node (ref "R13") (pin "2") (pinfunction "2_2") (pintype "passive"))
      (node (ref "R14") (pin "2") (pinfunction "2_2") (pintype "passive"))
      (node (ref "R15") (pin "2") (pinfunction "2_2") (pintype "passive"))
      (node (ref "R16") (pin "2") (pinfunction "2_2") (pintype "passive"))
      (node (ref "R4") (pin "1") (pinfunction "1_1") (pintype "passive"))
      (node (ref "R7") (pin "1") (pinfunction "1_1") (pintype "passive"))
      (node (ref "R8") (pin "2") (pinfunction "2_2") (pintype "passive"))
      (node (ref "R9") (pin "2") (pinfunction "2_2") (pintype "passive"))
      (node (ref "RESET") (pin "B") (pinfunction "S_B") (pintype "passive"))
      (node (ref "RESET") (pin "B'") (pinfunction "S1_B'") (pintype "passive"))
      (node (ref "SWITCH") (pin "S1") (pinfunction "S_S1") (pintype "passive"))
      (node (ref "SWITCH") (pin "S2") (pinfunction "S_S2") (pintype "passive"))
      (node (ref "U3") (pin "2") (pinfunction "GND_2") (pintype "power_in"))
      (node (ref "U4") (pin "P$B7") (pinfunction "VSS_P$B7") (pintype "power_in"))
      (node (ref "U4") (pin "P$F23") (pinfunction "VSS_PA_P$F23") (pintype "bidirectional"))
      (node (ref "U4") (pin "THERMPAD") (pinfunction "VSS_PAD_THERMPAD") (pintype "bidirectional"))
    )
    (net (code "41") (name "Net-(BATT-Pad2)") (class "Default")
      (node (ref "BATT") (pin "2") (pinfunction "2_2") (pintype "passive"))
      (node (ref "D2") (pin "A") (pinfunction "A_A") (pintype "passive"))
    )
    (net (code "42") (name "Net-(C9-Pad2)") (class "Default")
      (node (ref "C9") (pin "2") (pinfunction "2_2") (pintype "passive"))
      (node (ref "R1") (pin "1") (pinfunction "1_1") (pintype "passive"))
    )
    (net (code "43") (name "Net-(D1-PadC)") (class "Default")
      (node (ref "D1") (pin "C") (pinfunction "C_C") (pintype "passive"))
      (node (ref "D2") (pin "C") (pinfunction "C_C") (pintype "passive"))
      (node (ref "F1") (pin "1") (pinfunction "1_1") (pintype "passive"))
    )
    (net (code "44") (name "Net-(IC2-IN)") (class "Default")
      (node (ref "IC2") (pin "3") (pinfunction "IN_3") (pintype "input"))
      (node (ref "R1") (pin "2") (pinfunction "2_2") (pintype "passive"))
    )
    (net (code "45") (name "Net-(IC2-VO_N)") (class "Default")
      (node (ref "IC2") (pin "1") (pinfunction "VO_N_1") (pintype "output"))
      (node (ref "SP1") (pin "-") (pinfunction "-_-") (pintype "passive"))
    )
    (net (code "46") (name "Net-(IC2-VO_P)") (class "Default")
      (node (ref "IC2") (pin "6") (pinfunction "VO_P_6") (pintype "output"))
      (node (ref "SP1") (pin "+") (pinfunction "+_+") (pintype "passive"))
    )
    (net (code "47") (name "Net-(L-PadA)") (class "Default")
      (node (ref "L") (pin "A") (pinfunction "A_A") (pintype "passive"))
      (node (ref "R5") (pin "2") (pinfunction "2_2") (pintype "passive"))
    )
    (net (code "48") (name "Net-(LED1-DI)") (class "Default")
      (node (ref "LED1") (pin "1") (pinfunction "DI_1") (pintype "input"))
      (node (ref "LED2") (pin "3") (pinfunction "DO_3") (pintype "output"))
    )
    (net (code "49") (name "Net-(LED1-DO)") (class "Default")
      (node (ref "LED1") (pin "3") (pinfunction "DO_3") (pintype "output"))
      (node (ref "LED3") (pin "1") (pinfunction "DI_1") (pintype "input"))
    )
    (net (code "50") (name "Net-(LED3-DO)") (class "Default")
      (node (ref "LED3") (pin "3") (pinfunction "DO_3") (pintype "output"))
      (node (ref "LED4") (pin "1") (pinfunction "DI_1") (pintype "input"))
    )
    (net (code "51") (name "Net-(LED4-DO)") (class "Default")
      (node (ref "LED4") (pin "3") (pinfunction "DO_3") (pintype "output"))
      (node (ref "LED5") (pin "1") (pinfunction "DI_1") (pintype "input"))
    )
    (net (code "52") (name "Net-(LED6-DO)") (class "Default")
      (node (ref "LED6") (pin "3") (pinfunction "DO_3") (pintype "output"))
      (node (ref "LED7") (pin "1") (pinfunction "DI_1") (pintype "input"))
    )
    (net (code "53") (name "Net-(LED7-DO)") (class "Default")
      (node (ref "LED7") (pin "3") (pinfunction "DO_3") (pintype "output"))
      (node (ref "LED8") (pin "1") (pinfunction "DI_1") (pintype "input"))
    )
    (net (code "54") (name "Net-(LED8-DO)") (class "Default")
      (node (ref "LED8") (pin "3") (pinfunction "DO_3") (pintype "output"))
      (node (ref "LED9") (pin "1") (pinfunction "DI_1") (pintype "input"))
    )
    (net (code "55") (name "Net-(LED10-DI)") (class "Default")
      (node (ref "LED10") (pin "1") (pinfunction "DI_1") (pintype "input"))
      (node (ref "LED9") (pin "3") (pinfunction "DO_3") (pintype "output"))
    )
    (net (code "56") (name "Net-(LED10-DO)") (class "Default")
      (node (ref "LED10") (pin "3") (pinfunction "DO_3") (pintype "output"))
      (node (ref "LED2") (pin "1") (pinfunction "DI_1") (pintype "input"))
    )
    (net (code "57") (name "Net-(PWR-PadA)") (class "Default")
      (node (ref "PWR") (pin "A") (pinfunction "A_A") (pintype "passive"))
      (node (ref "R3") (pin "1") (pinfunction "1_1") (pintype "passive"))
    )
    (net (code "58") (name "Net-(U4-ANT)") (class "Default")
      (node (ref "C10") (pin "1") (pinfunction "1_1") (pintype "passive"))
      (node (ref "L1") (pin "1") (pinfunction "1_1") (pintype "passive"))
      (node (ref "U4") (pin "P$H23") (pinfunction "ANT_P$H23") (pintype "bidirectional"))
    )
    (net (code "59") (name "Net-(U4-XC1)") (class "Default")
      (node (ref "C13") (pin "1") (pinfunction "1_1") (pintype "passive"))
      (node (ref "U4") (pin "P$B24") (pinfunction "XC1_P$B24") (pintype "input"))
      (node (ref "Y1") (pin "1") (pinfunction "1_1") (pintype "passive"))
    )
    (net (code "60") (name "Net-(U4-XC2)") (class "Default")
      (node (ref "C12") (pin "1") (pinfunction "1_1") (pintype "passive"))
      (node (ref "U4") (pin "P$A23") (pinfunction "XC2_P$A23") (pintype "output"))
      (node (ref "Y1") (pin "3") (pinfunction "2_3") (pintype "passive"))
    )
    (net (code "61") (name "VBUS") (class "Default")
      (node (ref "C19") (pin "1") (pinfunction "1_1") (pintype "passive"))
      (node (ref "CN1") (pin "VBUS") (pinfunction "VBUS_VBUS") (pintype "power_in"))
      (node (ref "D1") (pin "A") (pinfunction "A_A") (pintype "passive"))
      (node (ref "U4") (pin "P$AD2") (pinfunction "VBUS_P$AD2") (pintype "power_in"))
    )
    (net (code "62") (name "VCC") (class "Default")
      (node (ref "C4") (pin "1") (pinfunction "1_1") (pintype "passive"))
      (node (ref "C5") (pin "1") (pinfunction "1_1") (pintype "passive"))
      (node (ref "F1") (pin "2") (pinfunction "2_2") (pintype "passive"))
      (node (ref "IC2") (pin "5") (pinfunction "VDD_5") (pintype "power_in"))
      (node (ref "U3") (pin "1") (pinfunction "IN_1") (pintype "power_in"))
      (node (ref "U3") (pin "3") (pinfunction "EN_3") (pintype "input"))
      (node (ref "VCC2") (pin "P$1") (pinfunction "SEW_P$1") (pintype "bidirectional"))
    )
    (net (code "63") (name "unconnected-(CN1-PadID)") (class "Default")
      (node (ref "CN1") (pin "ID") (pinfunction "ID_ID") (pintype "bidirectional"))
    )
    (net (code "64") (name "unconnected-(IC4-INT2-Pad9)") (class "Default")
      (node (ref "IC4") (pin "9") (pinfunction "INT2_9") (pintype "output"))
    )
    (net (code "65") (name "unconnected-(IC4-NC-Pad2)") (class "Default")
      (node (ref "IC4") (pin "2") (pinfunction "NC_2") (pintype "no_connect"))
    )
    (net (code "66") (name "unconnected-(IC4-NC-Pad3)") (class "Default")
      (node (ref "IC4") (pin "3") (pinfunction "NC_3") (pintype "no_connect"))
    )
    (net (code "67") (name "unconnected-(LED5-DO-Pad3)") (class "Default")
      (node (ref "LED5") (pin "3") (pinfunction "DO_3") (pintype "output"))
    )
    (net (code "68") (name "unconnected-(SWITCHA-O-PadO1)") (class "Default")
      (node (ref "SWITCH") (pin "O1") (pinfunction "O_O1") (pintype "passive"))
    )
    (net (code "69") (name "unconnected-(SWITCHB-O-PadO2)") (class "Default")
      (node (ref "SWITCH") (pin "O2") (pinfunction "O_O2") (pintype "passive"))
    )
    (net (code "70") (name "unconnected-(U3-P4-Pad4)") (class "Default")
      (node (ref "U3") (pin "4") (pinfunction "P4_4") (pintype "bidirectional"))
    )
    (net (code "71") (name "unconnected-(U4-DCC-PadP$B3)") (class "Default")
      (node (ref "U4") (pin "P$B3") (pinfunction "DCC_P$B3") (pintype "output"))
    )
    (net (code "72") (name "unconnected-(U4-DCCH-PadP$AB2)") (class "Default")
      (node (ref "U4") (pin "P$AB2") (pinfunction "DCCH_P$AB2") (pintype "bidirectional"))
    )
    (net (code "73") (name "unconnected-(U4-DEC2-PadP$A18)") (class "Default")
      (node (ref "U4") (pin "P$A18") (pinfunction "DEC2_P$A18") (pintype "bidirectional"))
    )
    (net (code "74") (name "unconnected-(U4-P0.00{slash}XL1-PadP$D2)") (class "Default")
      (node (ref "U4") (pin "P$D2") (pinfunction "P0.00/XL1_P$D2") (pintype "bidirectional"))
    )
    (net (code "75") (name "unconnected-(U4-P0.01{slash}XL2-PadP$F2)") (class "Default")
      (node (ref "U4") (pin "P$F2") (pinfunction "P0.01/XL2_P$F2") (pintype "bidirectional"))
    )
    (net (code "76") (name "unconnected-(U4-P0.06-PadP$L1)") (class "Default")
      (node (ref "U4") (pin "P$L1") (pinfunction "P0.06_P$L1") (pintype "bidirectional"))
    )
    (net (code "77") (name "unconnected-(U4-P0.07-PadP$M2)") (class "Default")
      (node (ref "U4") (pin "P$M2") (pinfunction "P0.07_P$M2") (pintype "bidirectional"))
    )
    (net (code "78") (name "unconnected-(U4-P0.08-PadP$N1)") (class "Default")
      (node (ref "U4") (pin "P$N1") (pinfunction "P0.08_P$N1") (pintype "bidirectional"))
    )
    (net (code "79") (name "unconnected-(U4-P0.09{slash}NFC1-PadP$L24)") (class "Default")
      (node (ref "U4") (pin "P$L24") (pinfunction "P0.09/NFC1_P$L24") (pintype "bidirectional"))
    )
    (net (code "80") (name "unconnected-(U4-P0.10{slash}NFC2-PadP$J24)") (class "Default")
      (node (ref "U4") (pin "P$J24") (pinfunction "P0.10/NFC2_P$J24") (pintype "bidirectional"))
    )
    (net (code "81") (name "unconnected-(U4-P0.11-PadP$T2)") (class "Default")
      (node (ref "U4") (pin "P$T2") (pinfunction "P0.11_P$T2") (pintype "bidirectional"))
    )
    (net (code "82") (name "unconnected-(U4-P0.12-PadP$U1)") (class "Default")
      (node (ref "U4") (pin "P$U1") (pinfunction "P0.12_P$U1") (pintype "bidirectional"))
    )
    (net (code "83") (name "unconnected-(U4-P0.20-PadP$AD16)") (class "Default")
      (node (ref "U4") (pin "P$AD16") (pinfunction "P0.20_P$AD16") (pintype "bidirectional"))
    )
    (net (code "84") (name "unconnected-(U4-P0.24-PadP$AD20)") (class "Default")
      (node (ref "U4") (pin "P$AD20") (pinfunction "P0.24_P$AD20") (pintype "bidirectional"))
    )
    (net (code "85") (name "unconnected-(U4-P0.25-PadP$AC21)") (class "Default")
      (node (ref "U4") (pin "P$AC21") (pinfunction "P0.25_P$AC21") (pintype "bidirectional"))
    )
    (net (code "86") (name "unconnected-(U4-P0.27-PadP$H2)") (class "Default")
      (node (ref "U4") (pin "P$H2") (pinfunction "P0.27_P$H2") (pintype "bidirectional"))
    )
    (net (code "87") (name "unconnected-(U4-P1.01-PadP$Y23)") (class "Default")
      (node (ref "U4") (pin "P$Y23") (pinfunction "P1.01_P$Y23") (pintype "bidirectional"))
    )
    (net (code "88") (name "unconnected-(U4-P1.03-PadP$V23)") (class "Default")
      (node (ref "U4") (pin "P$V23") (pinfunction "P1.03_P$V23") (pintype "bidirectional"))
    )
    (net (code "89") (name "unconnected-(U4-P1.05-PadP$T23)") (class "Default")
      (node (ref "U4") (pin "P$T23") (pinfunction "P1.05_P$T23") (pintype "bidirectional"))
    )
    (net (code "90") (name "unconnected-(U4-P1.07-PadP$P23)") (class "Default")
      (node (ref "U4") (pin "P$P23") (pinfunction "P1.07_P$P23") (pintype "bidirectional"))
    )
    (net (code "91") (name "unconnected-(U4-P1.08-PadP$P2)") (class "Default")
      (node (ref "U4") (pin "P$P2") (pinfunction "P1.08_P$P2") (pintype "bidirectional"))
    )
    (net (code "92") (name "unconnected-(U4-P1.09-PadP$R1)") (class "Default")
      (node (ref "U4") (pin "P$R1") (pinfunction "P1.09_P$R1") (pintype "bidirectional"))
    )
    (net (code "93") (name "unconnected-(U4-P1.11-PadP$B19)") (class "Default")
      (node (ref "U4") (pin "P$B19") (pinfunction "P1.11_P$B19") (pintype "bidirectional"))
    )
  )
)
